# xmas-tree.net
KiCad netlist of a schematic drawn in EAGLE
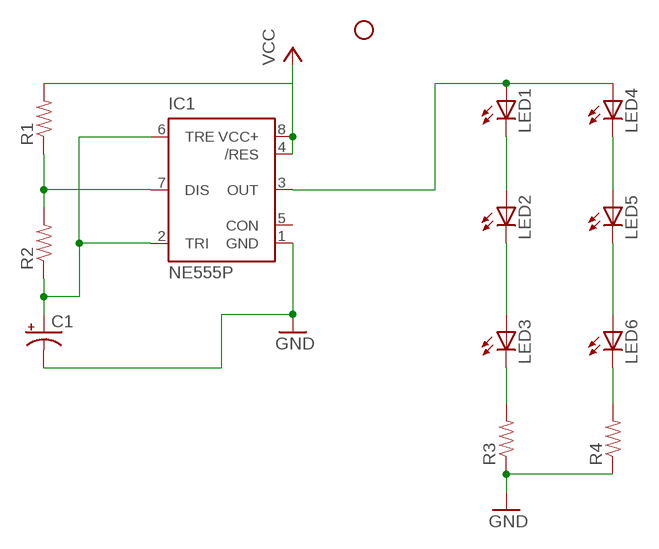
[diagram p0: schematic, sheet 1]

(export (version "E")
  (design (tool "Eeschema 10.0.6"))
  (components
    (comp (ref "C1")
      (value "CAP_POLPTH2")
      (footprint "eagle-import:CPOL-RADIAL-10UF-25V")
      (libsource (lib "eagle-import") (part "CAP_POLPTH2"))
    )
    (comp (ref "IC1")
      (value "NE555P")
      (footprint "eagle-import:DIL-08")
      (fields (field (name "MF") "Arrow Electronics") (field (name "MPN") "NE555N"))
      (libsource (lib "eagle-import") (part "NE555P"))
    )
    (comp (ref "LED1")
      (value "LED5MM")
      (footprint "eagle-import:LED5MM")
      (libsource (lib "eagle-import") (part "LED5MM"))
    )
    (comp (ref "LED2")
      (value "LED5MM")
      (footprint "eagle-import:LED5MM")
      (libsource (lib "eagle-import") (part "LED5MM"))
    )
    (comp (ref "LED3")
      (value "LED5MM")
      (footprint "eagle-import:LED5MM")
      (libsource (lib "eagle-import") (part "LED5MM"))
    )
    (comp (ref "LED4")
      (value "LED5MM")
      (footprint "eagle-import:LED5MM")
      (libsource (lib "eagle-import") (part "LED5MM"))
    )
    (comp (ref "LED5")
      (value "LED5MM")
      (footprint "eagle-import:LED5MM")
      (libsource (lib "eagle-import") (part "LED5MM"))
    )
    (comp (ref "LED6")
      (value "LED5MM")
      (footprint "eagle-import:LED5MM")
      (libsource (lib "eagle-import") (part "LED5MM"))
    )
    (comp (ref "R1")
      (value "RESISTORAXIAL-0.3")
      (footprint "eagle-import:AXIAL-0.3")
      (libsource (lib "eagle-import") (part "RESISTORAXIAL-0.3"))
    )
    (comp (ref "R2")
      (value "RESISTORAXIAL-0.3")
      (footprint "eagle-import:AXIAL-0.3")
      (libsource (lib "eagle-import") (part "RESISTORAXIAL-0.3"))
    )
    (comp (ref "R3")
      (value "RESISTORAXIAL-0.3")
      (footprint "eagle-import:AXIAL-0.3")
      (libsource (lib "eagle-import") (part "RESISTORAXIAL-0.3"))
    )
    (comp (ref "R4")
      (value "RESISTORAXIAL-0.3")
      (footprint "eagle-import:AXIAL-0.3")
      (libsource (lib "eagle-import") (part "RESISTORAXIAL-0.3"))
    )
    (comp (ref "STANDOFF1")
      (value "STAND-OFF")
      (footprint "eagle-import:STAND-OFF")
      (libsource (lib "eagle-import") (part "STAND-OFF"))
    )
  )
  (nets
    (net (code "1") (name "GND") (class "Default")
      (node (ref "C1") (pin "2") (pinfunction "-_2") (pintype "passive"))
      (node (ref "IC1") (pin "1") (pinfunction "GND_1") (pintype "power_in"))
      (node (ref "R3") (pin "P$1") (pinfunction "1_P$1") (pintype "passive"))
      (node (ref "R4") (pin "P$1") (pinfunction "1_P$1") (pintype "passive"))
    )
    (net (code "2") (name "Net-(C1-+)") (class "Default")
      (node (ref "C1") (pin "1") (pinfunction "+_1") (pintype "passive"))
      (node (ref "IC1") (pin "2") (pinfunction "TRI_2") (pintype "input"))
      (node (ref "IC1") (pin "6") (pinfunction "TRE_6") (pintype "input"))
      (node (ref "R2") (pin "P$1") (pinfunction "1_P$1") (pintype "passive"))
    )
    (net (code "3") (name "Net-(IC1-DIS)") (class "Default")
      (node (ref "IC1") (pin "7") (pinfunction "DIS_7") (pintype "input"))
      (node (ref "R1") (pin "P$1") (pinfunction "1_P$1") (pintype "passive"))
      (node (ref "R2") (pin "P$2") (pinfunction "2_P$2") (pintype "passive"))
    )
    (net (code "4") (name "Net-(IC1-OUT)") (class "Default")
      (node (ref "IC1") (pin "3") (pinfunction "OUT_3") (pintype "output"))
      (node (ref "LED1") (pin "A") (pinfunction "A_A") (pintype "passive"))
      (node (ref "LED4") (pin "A") (pinfunction "A_A") (pintype "passive"))
    )
    (net (code "5") (name "Net-(LED1-C)") (class "Default")
      (node (ref "LED1") (pin "K") (pinfunction "C_K") (pintype "passive"))
      (node (ref "LED2") (pin "A") (pinfunction "A_A") (pintype "passive"))
    )
    (net (code "6") (name "Net-(LED2-C)") (class "Default")
      (node (ref "LED2") (pin "K") (pinfunction "C_K") (pintype "passive"))
      (node (ref "LED3") (pin "A") (pinfunction "A_A") (pintype "passive"))
    )
    (net (code "7") (name "Net-(LED3-C)") (class "Default")
      (node (ref "LED3") (pin "K") (pinfunction "C_K") (pintype "passive"))
      (node (ref "R3") (pin "P$2") (pinfunction "2_P$2") (pintype "passive"))
    )
    (net (code "8") (name "Net-(LED4-C)") (class "Default")
      (node (ref "LED4") (pin "K") (pinfunction "C_K") (pintype "passive"))
      (node (ref "LED5") (pin "A") (pinfunction "A_A") (pintype "passive"))
    )
    (net (code "9") (name "Net-(LED5-C)") (class "Default")
      (node (ref "LED5") (pin "K") (pinfunction "C_K") (pintype "passive"))
      (node (ref "LED6") (pin "A") (pinfunction "A_A") (pintype "passive"))
    )
    (net (code "10") (name "Net-(LED6-C)") (class "Default")
      (node (ref "LED6") (pin "K") (pinfunction "C_K") (pintype "passive"))
      (node (ref "R4") (pin "P$2") (pinfunction "2_P$2") (pintype "passive"))
    )
    (net (code "11") (name "VCC") (class "Default")
      (node (ref "IC1") (pin "4") (pinfunction "/RES_4") (pintype "input"))
      (node (ref "IC1") (pin "8") (pinfunction "VCC+_8") (pintype "power_in"))
      (node (ref "R1") (pin "P$2") (pinfunction "2_P$2") (pintype "passive"))
    )
    (net (code "12") (name "unconnected-(IC1-CON-Pad5)") (class "Default")
      (node (ref "IC1") (pin "5") (pinfunction "CON_5") (pintype "input"))
    )
  )
)
